# 01_-_Main.net
KiCad netlist of a schematic drawn in Altium Designer
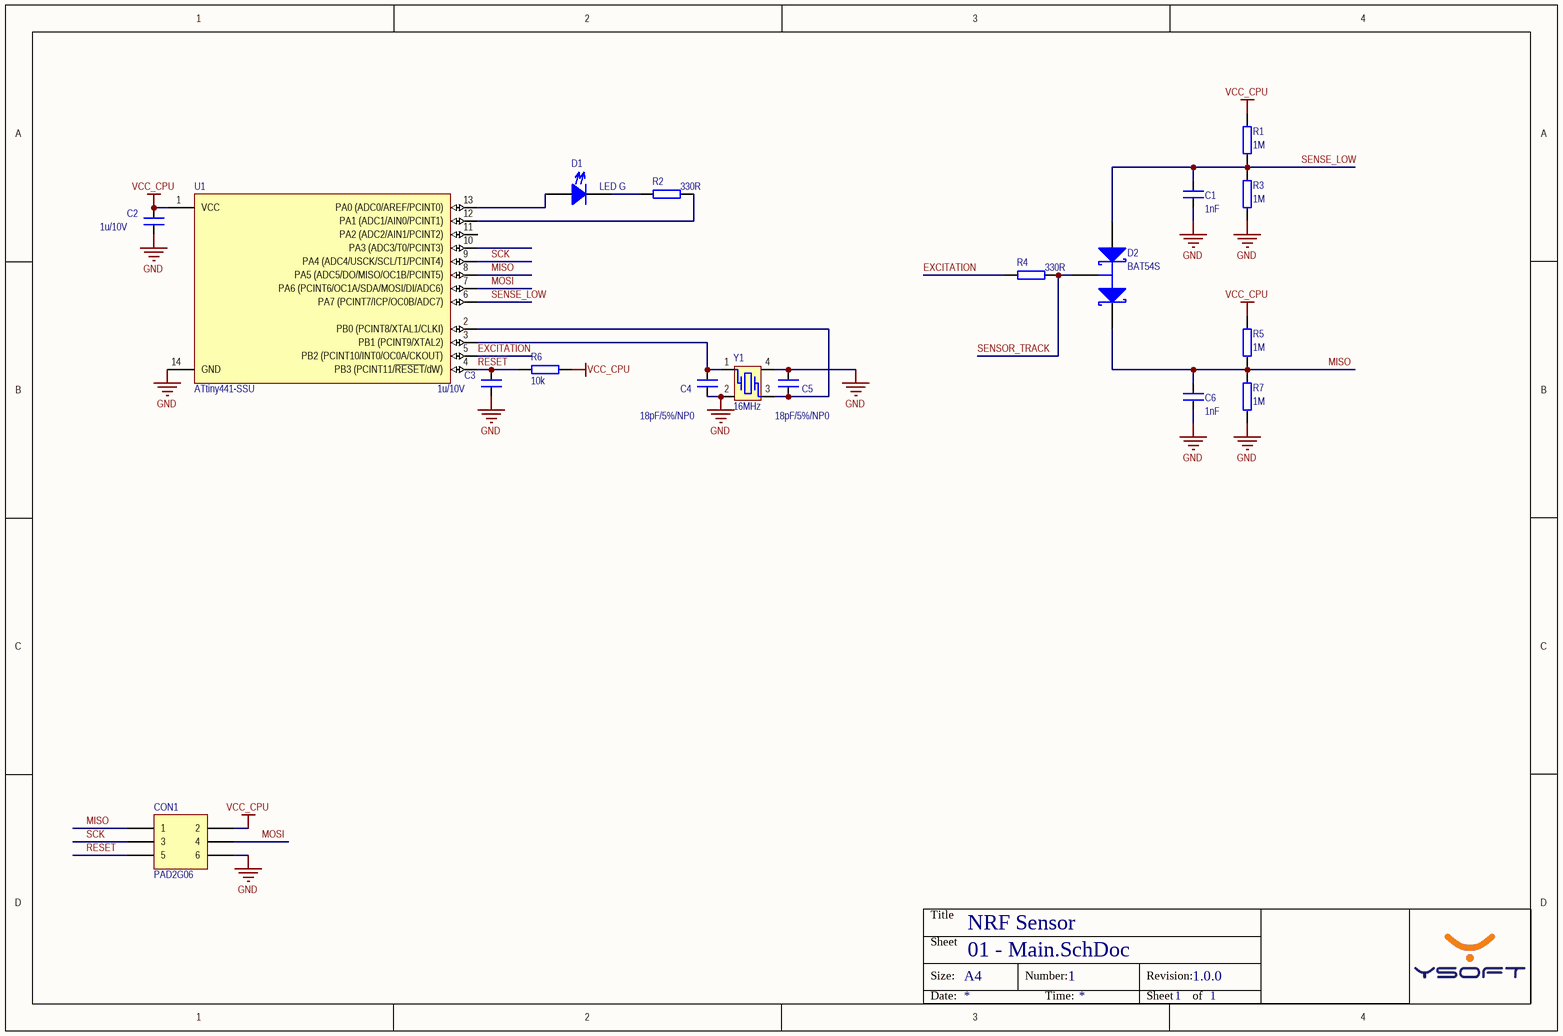
[diagram p0: 01 - Main.SchDoc]

(export (version "E")
  (design (tool "Eeschema 10.0.6"))
  (components
    (comp (ref "C1")
      (value "1nF")
      (footprint "C-0603")
      (description "SMD Ceramic Capacitor 0603 1nF/100V/5%")
      (libsource (lib "Personal Vault") (part "CapacitorNP"))
    )
    (comp (ref "C2")
      (value "1u/10V")
      (footprint "C-0603")
      (description "SMD Ceramic Capacitor 0603 1u/10V")
      (libsource (lib "Personal Vault") (part "CapacitorNP"))
    )
    (comp (ref "C3")
      (value "1u/10V")
      (footprint "C-0603")
      (description "SMD Ceramic Capacitor 0603 1u/10V")
      (libsource (lib "Personal Vault") (part "CapacitorNP"))
    )
    (comp (ref "C4")
      (value "18pF/5%/NP0")
      (footprint "C-0603")
      (description "SMD Ceramic Capacitor 0603 18pF/5%/NP0")
      (libsource (lib "Personal Vault") (part "CapacitorNP"))
    )
    (comp (ref "C5")
      (value "18pF/5%/NP0")
      (footprint "C-0603")
      (description "SMD Ceramic Capacitor 0603 18pF/5%/NP0")
      (libsource (lib "Personal Vault") (part "CapacitorNP"))
    )
    (comp (ref "C6")
      (value "1nF")
      (footprint "C-0603")
      (description "SMD Ceramic Capacitor 0603 1nF/100V/5%")
      (libsource (lib "Personal Vault") (part "CapacitorNP"))
    )
    (comp (ref "CON1")
      (value "PAD2G06")
      (footprint "HDR2X06S")
      (description "2x3pin dual row pads, 2.54mm")
      (libsource (lib "Personal Vault") (part "Header 3X2"))
    )
    (comp (ref "D1")
      (value "LED G")
      (footprint "LED-0603 GREEN")
      (description "LED; SMD; 0603; zelená; 4-15mcd; 1,6x0,8x1,1mm; 120°; 2,2÷2,5V; 20mA")
      (libsource (lib "Personal Vault") (part "LED"))
    )
    (comp (ref "D2")
      (value "BAT54S")
      (footprint "FAIR-SOT23-3_V")
      (description "Schottky Barrier Diode, 30 V, 0.2 A, -55 to 150 degC, 3-Pin SOT23, RoHS, Tape and Reel")
      (fields (field (name "TOLERANCE") "30ppm"))
      (libsource (lib "Altium Content Vault") (part "DSKY-AKC-3"))
    )
    (comp (ref "R1")
      (value "1M")
      (footprint "R-0603")
      (description "SMD Resistor 0603 1M")
      (libsource (lib "Personal Vault") (part "Resistor"))
    )
    (comp (ref "R2")
      (value "330R")
      (footprint "R-0603")
      (description "SMD Resistor 0603 330R")
      (libsource (lib "Personal Vault") (part "Resistor"))
    )
    (comp (ref "R3")
      (value "1M")
      (footprint "R-0603")
      (description "SMD Resistor 0603 1M")
      (libsource (lib "Personal Vault") (part "Resistor"))
    )
    (comp (ref "R4")
      (value "330R")
      (footprint "R-0603")
      (description "SMD Resistor 0603 330R")
      (libsource (lib "Personal Vault") (part "Resistor"))
    )
    (comp (ref "R5")
      (value "1M")
      (footprint "R-0603")
      (description "SMD Resistor 0603 1M")
      (libsource (lib "Personal Vault") (part "Resistor"))
    )
    (comp (ref "R6")
      (value "10k")
      (footprint "R-0603")
      (description "SMD Resistor 0603 10k")
      (libsource (lib "Personal Vault") (part "Resistor"))
    )
    (comp (ref "R7")
      (value "1M")
      (footprint "R-0603")
      (description "SMD Resistor 0603 1M")
      (libsource (lib "Personal Vault") (part "Resistor"))
    )
    (comp (ref "U1")
      (value "ATtiny441-SSU")
      (footprint "14S1_M")
      (libsource (lib "Altium Content Vault") (part "MC-8B-ATTINY24V-IL14"))
    )
    (comp (ref "Y1")
      (value "16MHz")
      (footprint "ASX3F")
      (description "Crystal 16 MHz SMD, package 3.2x2.5mm")
      (libsource (lib "Personal Vault") (part "Crystal 4 pin"))
    )
  )
  (nets
    (net (code "1") (name "/EXCITATION") (class "Default")
      (node (ref "R4") (pin "1") (pinfunction "1_1") (pintype "passive"))
      (node (ref "U1") (pin "5") (pinfunction "PB2_(PCINT10/INT0/OC0A/CKOUT)_5") (pintype "bidirectional"))
    )
    (net (code "2") (name "/MISO") (class "Default")
      (node (ref "C6") (pin "2") (pinfunction "2_2") (pintype "passive"))
      (node (ref "CON1") (pin "1") (pinfunction "1_1") (pintype "passive"))
      (node (ref "D2") (pin "2") (pinfunction "K_2") (pintype "passive"))
      (node (ref "R5") (pin "1") (pinfunction "1_1") (pintype "passive"))
      (node (ref "R7") (pin "2") (pinfunction "2_2") (pintype "passive"))
      (node (ref "U1") (pin "8") (pinfunction "PA5_(ADC5/DO/MISO/OC1B/PCINT5)_8") (pintype "bidirectional"))
    )
    (net (code "3") (name "/MOSI") (class "Default")
      (node (ref "CON1") (pin "4") (pinfunction "4_4") (pintype "passive"))
      (node (ref "U1") (pin "7") (pinfunction "PA6_(PCINT6/OC1A/SDA/MOSI/DI/ADC6)_7") (pintype "bidirectional"))
    )
    (net (code "4") (name "/RESET") (class "Default")
      (node (ref "C3") (pin "2") (pinfunction "2_2") (pintype "passive"))
      (node (ref "CON1") (pin "5") (pinfunction "5_5") (pintype "passive"))
      (node (ref "R6") (pin "1") (pinfunction "1_1") (pintype "passive"))
      (node (ref "U1") (pin "4") (pinfunction "PB3_(PCINT11/~{RESET}/dW)_4") (pintype "bidirectional"))
    )
    (net (code "5") (name "/SCK") (class "Default")
      (node (ref "CON1") (pin "3") (pinfunction "3_3") (pintype "passive"))
      (node (ref "U1") (pin "9") (pinfunction "PA4_(ADC4/USCK/SCL/T1/PCINT4)_9") (pintype "bidirectional"))
    )
    (net (code "6") (name "/SENSE_LOW") (class "Default")
      (node (ref "C1") (pin "2") (pinfunction "2_2") (pintype "passive"))
      (node (ref "D2") (pin "1") (pinfunction "A_1") (pintype "passive"))
      (node (ref "R1") (pin "1") (pinfunction "1_1") (pintype "passive"))
      (node (ref "R3") (pin "2") (pinfunction "2_2") (pintype "passive"))
      (node (ref "U1") (pin "6") (pinfunction "PA7_(PCINT7/ICP/OC0B/ADC7)_6") (pintype "bidirectional"))
    )
    (net (code "7") (name "/SENSOR_TRACK") (class "Default")
      (node (ref "D2") (pin "3") (pinfunction "C_3") (pintype "passive"))
      (node (ref "R4") (pin "2") (pinfunction "2_2") (pintype "passive"))
    )
    (net (code "8") (name "GND") (class "Default")
      (node (ref "C1") (pin "1") (pinfunction "1_1") (pintype "passive"))
      (node (ref "C2") (pin "1") (pinfunction "1_1") (pintype "passive"))
      (node (ref "C3") (pin "1") (pinfunction "1_1") (pintype "passive"))
      (node (ref "C4") (pin "1") (pinfunction "1_1") (pintype "passive"))
      (node (ref "C5") (pin "2") (pinfunction "2_2") (pintype "passive"))
      (node (ref "C6") (pin "1") (pinfunction "1_1") (pintype "passive"))
      (node (ref "CON1") (pin "6") (pinfunction "6_6") (pintype "passive"))
      (node (ref "R3") (pin "1") (pinfunction "1_1") (pintype "passive"))
      (node (ref "R7") (pin "1") (pinfunction "1_1") (pintype "passive"))
      (node (ref "U1") (pin "14") (pinfunction "GND_14") (pintype "power_in"))
      (node (ref "Y1") (pin "2") (pinfunction "2_2") (pintype "passive"))
      (node (ref "Y1") (pin "4") (pinfunction "4_4") (pintype "passive"))
    )
    (net (code "9") (name "Net-(D1-A)") (class "Default")
      (node (ref "D1") (pin "2") (pinfunction "A_2") (pintype "passive"))
      (node (ref "U1") (pin "13") (pinfunction "PA0_(ADC0/AREF/PCINT0)_13") (pintype "bidirectional"))
    )
    (net (code "10") (name "Net-(D1-K)") (class "Default")
      (node (ref "D1") (pin "1") (pinfunction "K_1") (pintype "passive"))
      (node (ref "R2") (pin "1") (pinfunction "1_1") (pintype "passive"))
    )
    (net (code "11") (name "Net-(U1-PA1_(ADC1{slash}AIN0{slash}PCINT1))") (class "Default")
      (node (ref "R2") (pin "2") (pinfunction "2_2") (pintype "passive"))
      (node (ref "U1") (pin "12") (pinfunction "PA1_(ADC1/AIN0/PCINT1)_12") (pintype "bidirectional"))
    )
    (net (code "12") (name "Net-(U1-PB0_(PCINT8{slash}XTAL1{slash}CLKI))") (class "Default")
      (node (ref "C5") (pin "1") (pinfunction "1_1") (pintype "passive"))
      (node (ref "U1") (pin "2") (pinfunction "PB0_(PCINT8/XTAL1/CLKI)_2") (pintype "bidirectional"))
      (node (ref "Y1") (pin "3") (pinfunction "3_3") (pintype "passive"))
    )
    (net (code "13") (name "Net-(U1-PB1_(PCINT9{slash}XTAL2))") (class "Default")
      (node (ref "C4") (pin "2") (pinfunction "2_2") (pintype "passive"))
      (node (ref "U1") (pin "3") (pinfunction "PB1_(PCINT9/XTAL2)_3") (pintype "bidirectional"))
      (node (ref "Y1") (pin "1") (pinfunction "1_1") (pintype "passive"))
    )
    (net (code "14") (name "VCC_CPU") (class "Default")
      (node (ref "C2") (pin "2") (pinfunction "2_2") (pintype "passive"))
      (node (ref "CON1") (pin "2") (pinfunction "2_2") (pintype "passive"))
      (node (ref "R1") (pin "2") (pinfunction "2_2") (pintype "passive"))
      (node (ref "R5") (pin "2") (pinfunction "2_2") (pintype "passive"))
      (node (ref "R6") (pin "2") (pinfunction "2_2") (pintype "passive"))
      (node (ref "U1") (pin "1") (pinfunction "VCC_1") (pintype "power_in"))
    )
    (net (code "15") (name "unconnected-(U1-PA2_(ADC2{slash}AIN1{slash}PCINT2)-Pad11)") (class "Default")
      (node (ref "U1") (pin "11") (pinfunction "PA2_(ADC2/AIN1/PCINT2)_11") (pintype "bidirectional"))
    )
    (net (code "16") (name "unconnected-(U1-PA3_(ADC3{slash}T0{slash}PCINT3)-Pad10)") (class "Default")
      (node (ref "U1") (pin "10") (pinfunction "PA3_(ADC3/T0/PCINT3)_10") (pintype "bidirectional"))
    )
  )
)
